# Pendulum_Lamp_PCB.net
KiCad netlist of a schematic drawn in EAGLE
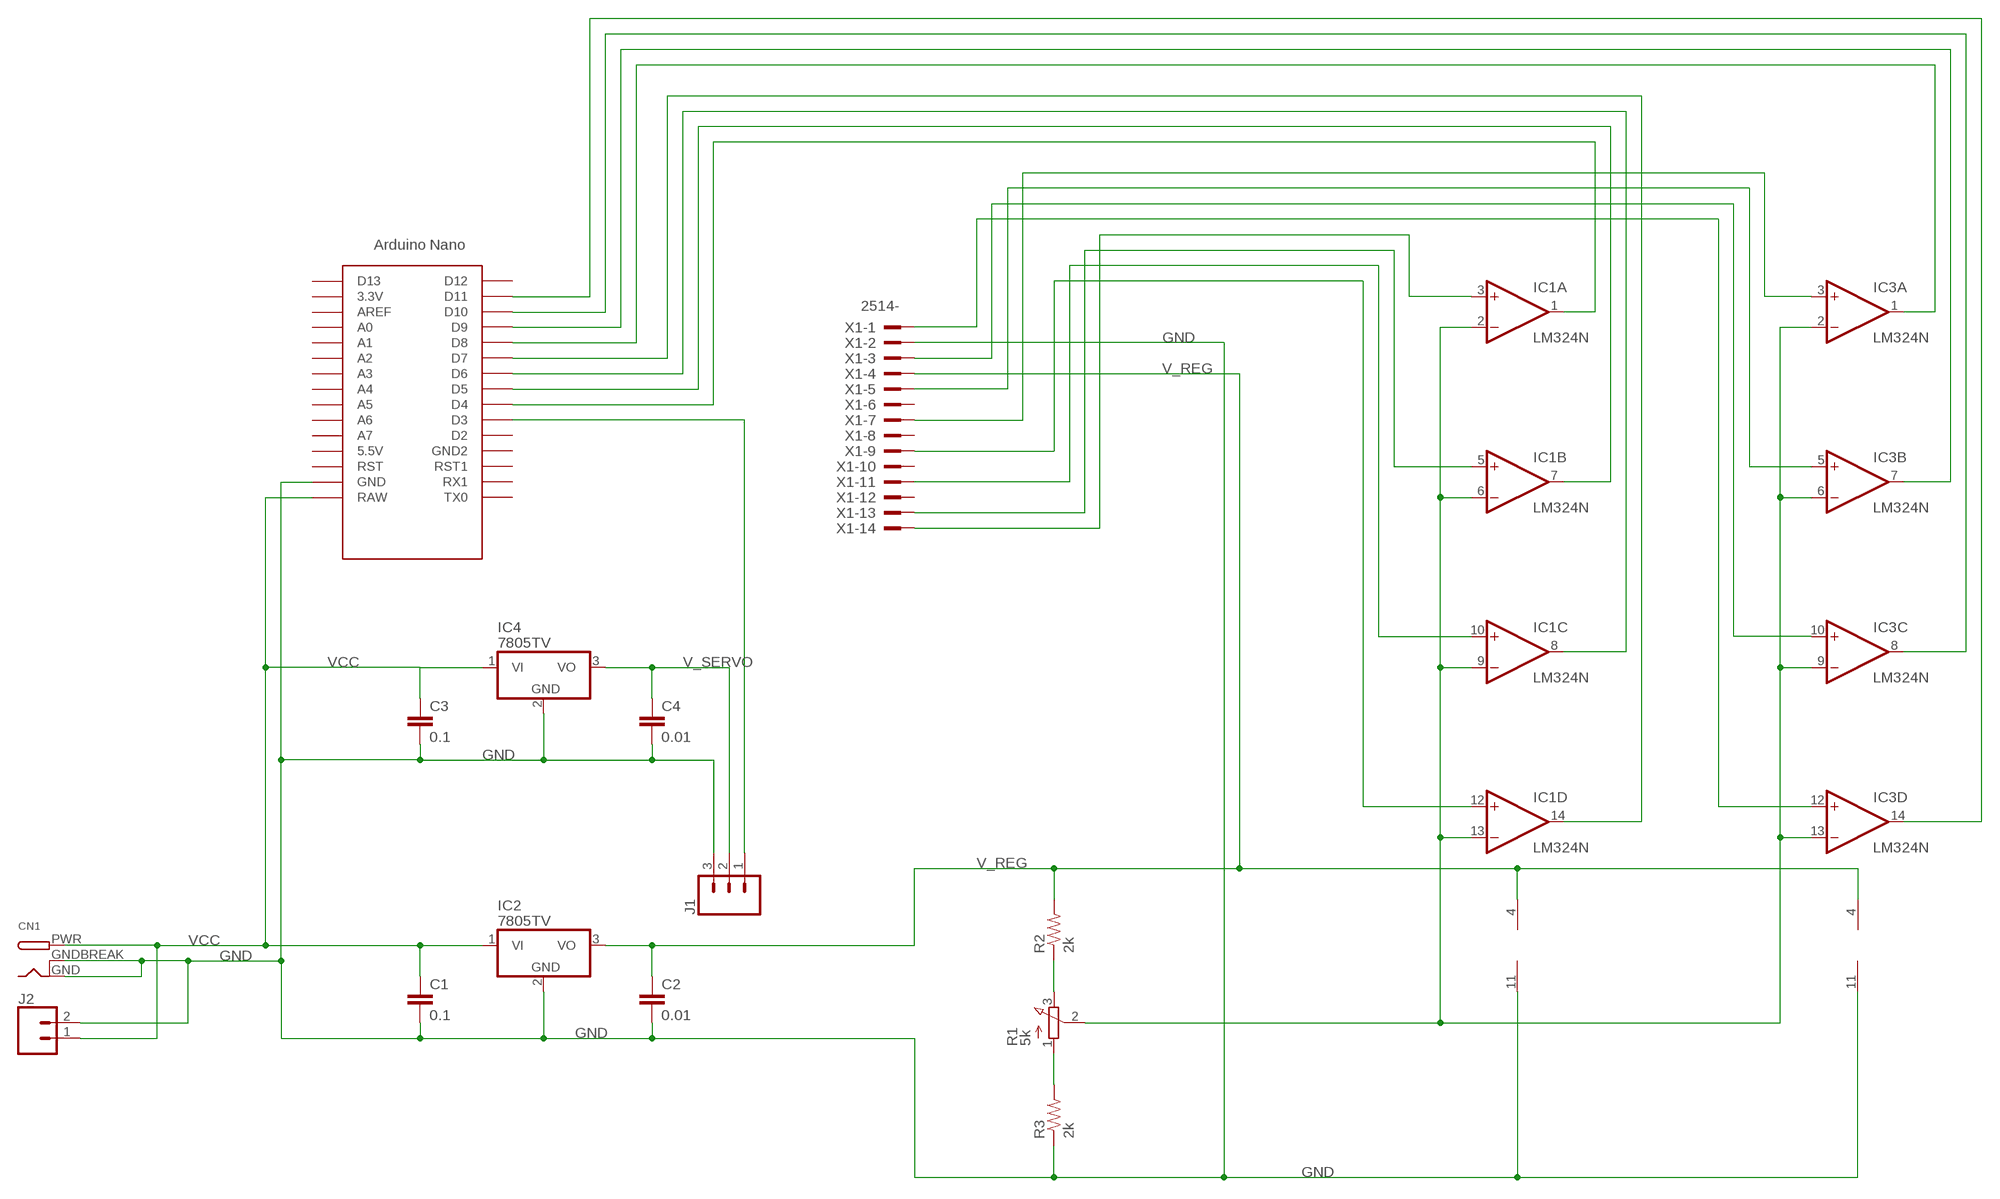
[diagram p0: schematic, sheet 1]
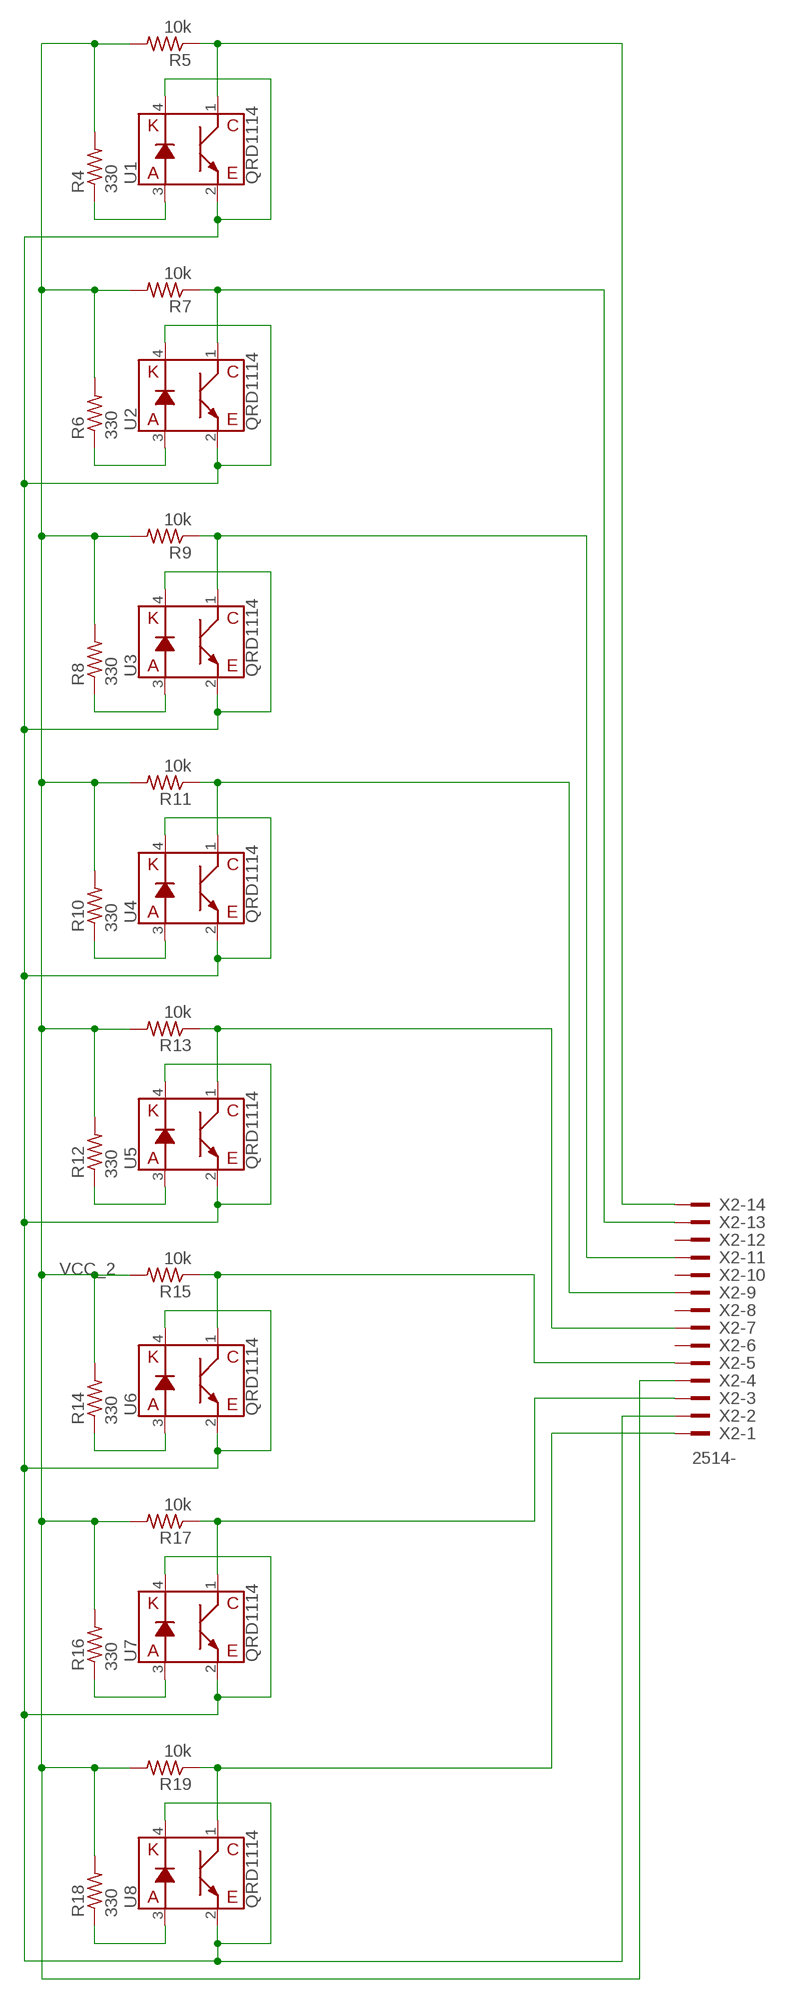
[diagram p1: schematic, sheet 2]

(export (version "E")
  (design (tool "Eeschema 10.0.6"))
  (components
    (comp (ref "R4")
      (value "330")
      (footprint "eagle-import:0204_7")
      (libsource (lib "eagle-import") (part "R-US_0204/7"))
    )
    (comp (ref "R5")
      (value "10k")
      (footprint "eagle-import:0204_7")
      (libsource (lib "eagle-import") (part "R-US_0204/7"))
    )
    (comp (ref "R6")
      (value "330")
      (footprint "eagle-import:0204_7")
      (libsource (lib "eagle-import") (part "R-US_0204/7"))
    )
    (comp (ref "R7")
      (value "10k")
      (footprint "eagle-import:0204_7")
      (libsource (lib "eagle-import") (part "R-US_0204/7"))
    )
    (comp (ref "R8")
      (value "330")
      (footprint "eagle-import:0204_7")
      (libsource (lib "eagle-import") (part "R-US_0204/7"))
    )
    (comp (ref "R9")
      (value "10k")
      (footprint "eagle-import:0204_7")
      (libsource (lib "eagle-import") (part "R-US_0204/7"))
    )
    (comp (ref "R10")
      (value "330")
      (footprint "eagle-import:0204_7")
      (libsource (lib "eagle-import") (part "R-US_0204/7"))
    )
    (comp (ref "R11")
      (value "10k")
      (footprint "eagle-import:0204_7")
      (libsource (lib "eagle-import") (part "R-US_0204/7"))
    )
    (comp (ref "R12")
      (value "330")
      (footprint "eagle-import:0204_7")
      (libsource (lib "eagle-import") (part "R-US_0204/7"))
    )
    (comp (ref "R13")
      (value "10k")
      (footprint "eagle-import:0204_7")
      (libsource (lib "eagle-import") (part "R-US_0204/7"))
    )
    (comp (ref "R14")
      (value "330")
      (footprint "eagle-import:0204_7")
      (libsource (lib "eagle-import") (part "R-US_0204/7"))
    )
    (comp (ref "R15")
      (value "10k")
      (footprint "eagle-import:0204_7")
      (libsource (lib "eagle-import") (part "R-US_0204/7"))
    )
    (comp (ref "R16")
      (value "330")
      (footprint "eagle-import:0204_7")
      (libsource (lib "eagle-import") (part "R-US_0204/7"))
    )
    (comp (ref "R17")
      (value "10k")
      (footprint "eagle-import:0204_7")
      (libsource (lib "eagle-import") (part "R-US_0204/7"))
    )
    (comp (ref "R18")
      (value "330")
      (footprint "eagle-import:0204_7")
      (libsource (lib "eagle-import") (part "R-US_0204/7"))
    )
    (comp (ref "R19")
      (value "10k")
      (footprint "eagle-import:0204_7")
      (libsource (lib "eagle-import") (part "R-US_0204/7"))
    )
    (comp (ref "U1")
      (value "QRD1114")
      (footprint "eagle-import:QRD1114")
      (libsource (lib "eagle-import") (part "QRD1114"))
    )
    (comp (ref "U2")
      (value "QRD1114")
      (footprint "eagle-import:QRD1114")
      (libsource (lib "eagle-import") (part "QRD1114"))
    )
    (comp (ref "U3")
      (value "QRD1114")
      (footprint "eagle-import:QRD1114")
      (libsource (lib "eagle-import") (part "QRD1114"))
    )
    (comp (ref "U4")
      (value "QRD1114")
      (footprint "eagle-import:QRD1114")
      (libsource (lib "eagle-import") (part "QRD1114"))
    )
    (comp (ref "U5")
      (value "QRD1114")
      (footprint "eagle-import:QRD1114")
      (libsource (lib "eagle-import") (part "QRD1114"))
    )
    (comp (ref "U6")
      (value "QRD1114")
      (footprint "eagle-import:QRD1114")
      (libsource (lib "eagle-import") (part "QRD1114"))
    )
    (comp (ref "U7")
      (value "QRD1114")
      (footprint "eagle-import:QRD1114")
      (libsource (lib "eagle-import") (part "QRD1114"))
    )
    (comp (ref "U8")
      (value "QRD1114")
      (footprint "eagle-import:QRD1114")
      (libsource (lib "eagle-import") (part "QRD1114"))
    )
    (comp (ref "X2")
      (value "2514-")
      (footprint "eagle-import:PAK100_2500-14")
      (libsource (lib "eagle-import") (part "2514-"))
    )
    (comp (ref "C1")
      (value "0.1")
      (footprint "eagle-import:C025-030X050")
      (libsource (lib "eagle-import") (part "C-EU025-030X050"))
    )
    (comp (ref "C2")
      (value "0.01")
      (footprint "eagle-import:C025-030X050")
      (libsource (lib "eagle-import") (part "C-EU025-030X050"))
    )
    (comp (ref "C3")
      (value "0.1")
      (footprint "eagle-import:C025-030X050")
      (libsource (lib "eagle-import") (part "C-EU025-030X050"))
    )
    (comp (ref "C4")
      (value "0.01")
      (footprint "eagle-import:C025-030X050")
      (libsource (lib "eagle-import") (part "C-EU025-030X050"))
    )
    (comp (ref "CN1")
      (value "DCBARRELPTH")
      (footprint "eagle-import:DCJACK_2MM_PTH")
      (libsource (lib "eagle-import") (part "DCBARRELPTH"))
    )
    (comp (ref "IC1")
      (value "LM324N")
      (footprint "eagle-import:DIL14")
      (libsource (lib "eagle-import") (part "LM324N"))
    )
    (comp (ref "IC2")
      (value "7805TV")
      (footprint "eagle-import:TO220V")
      (libsource (lib "eagle-import") (part "78TV05"))
    )
    (comp (ref "IC3")
      (value "LM324N")
      (footprint "eagle-import:DIL14")
      (libsource (lib "eagle-import") (part "LM324N"))
    )
    (comp (ref "IC4")
      (value "7805TV")
      (footprint "eagle-import:TO220V")
      (libsource (lib "eagle-import") (part "78TV05"))
    )
    (comp (ref "J1")
      (value "CONN_03LONGPADS")
      (footprint "eagle-import:1X03_LONGPADS")
      (libsource (lib "eagle-import") (part "CONN_03LONGPADS"))
    )
    (comp (ref "J2")
      (value "CONN_023.5MM_LOCK")
      (footprint "eagle-import:SCREWTERMINAL-3.5MM-2_LOCK")
      (libsource (lib "eagle-import") (part "CONN_023.5MM_LOCK"))
    )
    (comp (ref "R1")
      (value "5k")
      (footprint "eagle-import:3RP_1610N")
      (libsource (lib "eagle-import") (part "3RP/1610N"))
    )
    (comp (ref "R2")
      (value "2k")
      (footprint "eagle-import:0204_7")
      (libsource (lib "eagle-import") (part "R-US_0204/7"))
    )
    (comp (ref "R3")
      (value "2k")
      (footprint "eagle-import:0204_7")
      (libsource (lib "eagle-import") (part "R-US_0204/7"))
    )
    (comp (ref "U$1")
      (value "NANO")
      (footprint "eagle-import:NANO")
      (libsource (lib "eagle-import") (part "NANO"))
    )
    (comp (ref "X1")
      (value "2514-")
      (footprint "eagle-import:PAK100_2500-14")
      (libsource (lib "eagle-import") (part "2514-"))
    )
  )
  (nets
    (net (code "1") (name "GND") (class "Default")
      (node (ref "C1") (pin "2") (pinfunction "2_2") (pintype "passive"))
      (node (ref "C2") (pin "2") (pinfunction "2_2") (pintype "passive"))
      (node (ref "C3") (pin "2") (pinfunction "2_2") (pintype "passive"))
      (node (ref "C4") (pin "2") (pinfunction "2_2") (pintype "passive"))
      (node (ref "CN1") (pin "GND") (pinfunction "GND_GND") (pintype "power_in"))
      (node (ref "CN1") (pin "GNDBREAK") (pinfunction "GNDBREAK_GNDBREAK") (pintype "power_in"))
      (node (ref "IC1") (pin "11") (pinfunction "V-_11") (pintype "power_in"))
      (node (ref "IC2") (pin "2") (pinfunction "GND_2") (pintype "passive"))
      (node (ref "IC3") (pin "11") (pinfunction "V-_11") (pintype "power_in"))
      (node (ref "IC4") (pin "2") (pinfunction "GND_2") (pintype "passive"))
      (node (ref "J1") (pin "3") (pinfunction "3_3") (pintype "passive"))
      (node (ref "J2") (pin "2") (pinfunction "2_2") (pintype "passive"))
      (node (ref "R3") (pin "1") (pinfunction "1_1") (pintype "passive"))
      (node (ref "U$1") (pin "GND") (pinfunction "GND_GND") (pintype "bidirectional"))
      (node (ref "X1") (pin "2") (pinfunction "KL_2") (pintype "passive"))
    )
    (net (code "2") (name "Net-(IC1A-+IN)") (class "Default")
      (node (ref "IC1") (pin "3") (pinfunction "+IN_3") (pintype "input"))
      (node (ref "X1") (pin "14") (pinfunction "KL_14") (pintype "passive"))
    )
    (net (code "3") (name "Net-(IC1A--IN)") (class "Default")
      (node (ref "IC1") (pin "13") (pinfunction "-IN_13") (pintype "input"))
      (node (ref "IC1") (pin "2") (pinfunction "-IN_2") (pintype "input"))
      (node (ref "IC1") (pin "6") (pinfunction "-IN_6") (pintype "input"))
      (node (ref "IC1") (pin "9") (pinfunction "-IN_9") (pintype "input"))
      (node (ref "IC3") (pin "13") (pinfunction "-IN_13") (pintype "input"))
      (node (ref "IC3") (pin "2") (pinfunction "-IN_2") (pintype "input"))
      (node (ref "IC3") (pin "6") (pinfunction "-IN_6") (pintype "input"))
      (node (ref "IC3") (pin "9") (pinfunction "-IN_9") (pintype "input"))
      (node (ref "R1") (pin "2") (pinfunction "S_2") (pintype "passive"))
    )
    (net (code "4") (name "Net-(IC1A-OUT)") (class "Default")
      (node (ref "IC1") (pin "1") (pinfunction "OUT_1") (pintype "output"))
      (node (ref "U$1") (pin "D4") (pinfunction "D4_D4") (pintype "bidirectional"))
    )
    (net (code "5") (name "Net-(IC1B-+IN)") (class "Default")
      (node (ref "IC1") (pin "5") (pinfunction "+IN_5") (pintype "input"))
      (node (ref "X1") (pin "13") (pinfunction "KL_13") (pintype "passive"))
    )
    (net (code "6") (name "Net-(IC1B-OUT)") (class "Default")
      (node (ref "IC1") (pin "7") (pinfunction "OUT_7") (pintype "output"))
      (node (ref "U$1") (pin "D5") (pinfunction "D5_D5") (pintype "bidirectional"))
    )
    (net (code "7") (name "Net-(IC1C-+IN)") (class "Default")
      (node (ref "IC1") (pin "10") (pinfunction "+IN_10") (pintype "input"))
      (node (ref "X1") (pin "11") (pinfunction "KL_11") (pintype "passive"))
    )
    (net (code "8") (name "Net-(IC1C-OUT)") (class "Default")
      (node (ref "IC1") (pin "8") (pinfunction "OUT_8") (pintype "output"))
      (node (ref "U$1") (pin "D6") (pinfunction "D6_D6") (pintype "bidirectional"))
    )
    (net (code "9") (name "Net-(IC1D-+IN)") (class "Default")
      (node (ref "IC1") (pin "12") (pinfunction "+IN_12") (pintype "input"))
      (node (ref "X1") (pin "9") (pinfunction "KL_9") (pintype "passive"))
    )
    (net (code "10") (name "Net-(IC1D-OUT)") (class "Default")
      (node (ref "IC1") (pin "14") (pinfunction "OUT_14") (pintype "output"))
      (node (ref "U$1") (pin "D7") (pinfunction "D7_D7") (pintype "bidirectional"))
    )
    (net (code "11") (name "Net-(IC3A-+IN)") (class "Default")
      (node (ref "IC3") (pin "3") (pinfunction "+IN_3") (pintype "input"))
      (node (ref "X1") (pin "7") (pinfunction "KL_7") (pintype "passive"))
    )
    (net (code "12") (name "Net-(IC3A-OUT)") (class "Default")
      (node (ref "IC3") (pin "1") (pinfunction "OUT_1") (pintype "output"))
      (node (ref "U$1") (pin "D8") (pinfunction "D8_D8") (pintype "bidirectional"))
    )
    (net (code "13") (name "Net-(IC3B-+IN)") (class "Default")
      (node (ref "IC3") (pin "5") (pinfunction "+IN_5") (pintype "input"))
      (node (ref "X1") (pin "5") (pinfunction "KL_5") (pintype "passive"))
    )
    (net (code "14") (name "Net-(IC3B-OUT)") (class "Default")
      (node (ref "IC3") (pin "7") (pinfunction "OUT_7") (pintype "output"))
      (node (ref "U$1") (pin "D9") (pinfunction "D9_D9") (pintype "bidirectional"))
    )
    (net (code "15") (name "Net-(IC3C-+IN)") (class "Default")
      (node (ref "IC3") (pin "10") (pinfunction "+IN_10") (pintype "input"))
      (node (ref "X1") (pin "3") (pinfunction "KL_3") (pintype "passive"))
    )
    (net (code "16") (name "Net-(IC3C-OUT)") (class "Default")
      (node (ref "IC3") (pin "8") (pinfunction "OUT_8") (pintype "output"))
      (node (ref "U$1") (pin "D10") (pinfunction "D10_D10") (pintype "bidirectional"))
    )
    (net (code "17") (name "Net-(IC3D-+IN)") (class "Default")
      (node (ref "IC3") (pin "12") (pinfunction "+IN_12") (pintype "input"))
      (node (ref "X1") (pin "1") (pinfunction "KL_1") (pintype "passive"))
    )
    (net (code "18") (name "Net-(IC3D-OUT)") (class "Default")
      (node (ref "IC3") (pin "14") (pinfunction "OUT_14") (pintype "output"))
      (node (ref "U$1") (pin "D11") (pinfunction "D11_D11") (pintype "bidirectional"))
    )
    (net (code "19") (name "Net-(J1-Pad1)") (class "Default")
      (node (ref "J1") (pin "1") (pinfunction "1_1") (pintype "passive"))
      (node (ref "U$1") (pin "D3") (pinfunction "D3_D3") (pintype "bidirectional"))
    )
    (net (code "20") (name "Net-(R1-A)") (class "Default")
      (node (ref "R1") (pin "1") (pinfunction "A_1") (pintype "passive"))
      (node (ref "R3") (pin "2") (pinfunction "2_2") (pintype "passive"))
    )
    (net (code "21") (name "Net-(R1-E)") (class "Default")
      (node (ref "R1") (pin "3") (pinfunction "E_3") (pintype "passive"))
      (node (ref "R2") (pin "1") (pinfunction "1_1") (pintype "passive"))
    )
    (net (code "22") (name "Net-(U1-A)") (class "Default")
      (node (ref "R4") (pin "1") (pinfunction "1_1") (pintype "passive"))
      (node (ref "U1") (pin "3") (pinfunction "A_3") (pintype "bidirectional"))
    )
    (net (code "23") (name "Net-(U1-C)") (class "Default")
      (node (ref "R5") (pin "1") (pinfunction "1_1") (pintype "passive"))
      (node (ref "U1") (pin "1") (pinfunction "C_1") (pintype "bidirectional"))
      (node (ref "X2") (pin "14") (pinfunction "KL_14") (pintype "passive"))
    )
    (net (code "24") (name "Net-(U1-E)") (class "Default")
      (node (ref "U1") (pin "2") (pinfunction "E_2") (pintype "bidirectional"))
      (node (ref "U1") (pin "4") (pinfunction "K_4") (pintype "bidirectional"))
      (node (ref "U2") (pin "2") (pinfunction "E_2") (pintype "bidirectional"))
      (node (ref "U2") (pin "4") (pinfunction "K_4") (pintype "bidirectional"))
      (node (ref "U3") (pin "2") (pinfunction "E_2") (pintype "bidirectional"))
      (node (ref "U3") (pin "4") (pinfunction "K_4") (pintype "bidirectional"))
      (node (ref "U4") (pin "2") (pinfunction "E_2") (pintype "bidirectional"))
      (node (ref "U4") (pin "4") (pinfunction "K_4") (pintype "bidirectional"))
      (node (ref "U5") (pin "2") (pinfunction "E_2") (pintype "bidirectional"))
      (node (ref "U5") (pin "4") (pinfunction "K_4") (pintype "bidirectional"))
      (node (ref "U6") (pin "2") (pinfunction "E_2") (pintype "bidirectional"))
      (node (ref "U6") (pin "4") (pinfunction "K_4") (pintype "bidirectional"))
      (node (ref "U7") (pin "2") (pinfunction "E_2") (pintype "bidirectional"))
      (node (ref "U7") (pin "4") (pinfunction "K_4") (pintype "bidirectional"))
      (node (ref "U8") (pin "2") (pinfunction "E_2") (pintype "bidirectional"))
      (node (ref "U8") (pin "4") (pinfunction "K_4") (pintype "bidirectional"))
      (node (ref "X2") (pin "2") (pinfunction "KL_2") (pintype "passive"))
    )
    (net (code "25") (name "Net-(U2-A)") (class "Default")
      (node (ref "R6") (pin "1") (pinfunction "1_1") (pintype "passive"))
      (node (ref "U2") (pin "3") (pinfunction "A_3") (pintype "bidirectional"))
    )
    (net (code "26") (name "Net-(U2-C)") (class "Default")
      (node (ref "R7") (pin "1") (pinfunction "1_1") (pintype "passive"))
      (node (ref "U2") (pin "1") (pinfunction "C_1") (pintype "bidirectional"))
      (node (ref "X2") (pin "13") (pinfunction "KL_13") (pintype "passive"))
    )
    (net (code "27") (name "Net-(U3-A)") (class "Default")
      (node (ref "R8") (pin "1") (pinfunction "1_1") (pintype "passive"))
      (node (ref "U3") (pin "3") (pinfunction "A_3") (pintype "bidirectional"))
    )
    (net (code "28") (name "Net-(U3-C)") (class "Default")
      (node (ref "R9") (pin "1") (pinfunction "1_1") (pintype "passive"))
      (node (ref "U3") (pin "1") (pinfunction "C_1") (pintype "bidirectional"))
      (node (ref "X2") (pin "11") (pinfunction "KL_11") (pintype "passive"))
    )
    (net (code "29") (name "Net-(U4-A)") (class "Default")
      (node (ref "R10") (pin "1") (pinfunction "1_1") (pintype "passive"))
      (node (ref "U4") (pin "3") (pinfunction "A_3") (pintype "bidirectional"))
    )
    (net (code "30") (name "Net-(U4-C)") (class "Default")
      (node (ref "R11") (pin "1") (pinfunction "1_1") (pintype "passive"))
      (node (ref "U4") (pin "1") (pinfunction "C_1") (pintype "bidirectional"))
      (node (ref "X2") (pin "9") (pinfunction "KL_9") (pintype "passive"))
    )
    (net (code "31") (name "Net-(U5-A)") (class "Default")
      (node (ref "R12") (pin "1") (pinfunction "1_1") (pintype "passive"))
      (node (ref "U5") (pin "3") (pinfunction "A_3") (pintype "bidirectional"))
    )
    (net (code "32") (name "Net-(U5-C)") (class "Default")
      (node (ref "R13") (pin "1") (pinfunction "1_1") (pintype "passive"))
      (node (ref "U5") (pin "1") (pinfunction "C_1") (pintype "bidirectional"))
      (node (ref "X2") (pin "7") (pinfunction "KL_7") (pintype "passive"))
    )
    (net (code "33") (name "Net-(U6-A)") (class "Default")
      (node (ref "R14") (pin "1") (pinfunction "1_1") (pintype "passive"))
      (node (ref "U6") (pin "3") (pinfunction "A_3") (pintype "bidirectional"))
    )
    (net (code "34") (name "Net-(U6-C)") (class "Default")
      (node (ref "R15") (pin "1") (pinfunction "1_1") (pintype "passive"))
      (node (ref "U6") (pin "1") (pinfunction "C_1") (pintype "bidirectional"))
      (node (ref "X2") (pin "5") (pinfunction "KL_5") (pintype "passive"))
    )
    (net (code "35") (name "Net-(U7-A)") (class "Default")
      (node (ref "R16") (pin "1") (pinfunction "1_1") (pintype "passive"))
      (node (ref "U7") (pin "3") (pinfunction "A_3") (pintype "bidirectional"))
    )
    (net (code "36") (name "Net-(U7-C)") (class "Default")
      (node (ref "R17") (pin "1") (pinfunction "1_1") (pintype "passive"))
      (node (ref "U7") (pin "1") (pinfunction "C_1") (pintype "bidirectional"))
      (node (ref "X2") (pin "3") (pinfunction "KL_3") (pintype "passive"))
    )
    (net (code "37") (name "Net-(U8-A)") (class "Default")
      (node (ref "R18") (pin "1") (pinfunction "1_1") (pintype "passive"))
      (node (ref "U8") (pin "3") (pinfunction "A_3") (pintype "bidirectional"))
    )
    (net (code "38") (name "Net-(U8-C)") (class "Default")
      (node (ref "R19") (pin "1") (pinfunction "1_1") (pintype "passive"))
      (node (ref "U8") (pin "1") (pinfunction "C_1") (pintype "bidirectional"))
      (node (ref "X2") (pin "1") (pinfunction "KL_1") (pintype "passive"))
    )
    (net (code "39") (name "VCC") (class "Default")
      (node (ref "C1") (pin "1") (pinfunction "1_1") (pintype "passive"))
      (node (ref "C3") (pin "1") (pinfunction "1_1") (pintype "passive"))
      (node (ref "CN1") (pin "PWR") (pinfunction "PWR_PWR") (pintype "power_in"))
      (node (ref "IC2") (pin "1") (pinfunction "VI_1") (pintype "input"))
      (node (ref "IC4") (pin "1") (pinfunction "VI_1") (pintype "input"))
      (node (ref "J2") (pin "1") (pinfunction "1_1") (pintype "passive"))
      (node (ref "U$1") (pin "RAW") (pinfunction "RAW_RAW") (pintype "bidirectional"))
    )
    (net (code "40") (name "VCC_2") (class "Default")
      (node (ref "R10") (pin "2") (pinfunction "2_2") (pintype "passive"))
      (node (ref "R11") (pin "2") (pinfunction "2_2") (pintype "passive"))
      (node (ref "R12") (pin "2") (pinfunction "2_2") (pintype "passive"))
      (node (ref "R13") (pin "2") (pinfunction "2_2") (pintype "passive"))
      (node (ref "R14") (pin "2") (pinfunction "2_2") (pintype "passive"))
      (node (ref "R15") (pin "2") (pinfunction "2_2") (pintype "passive"))
      (node (ref "R16") (pin "2") (pinfunction "2_2") (pintype "passive"))
      (node (ref "R17") (pin "2") (pinfunction "2_2") (pintype "passive"))
      (node (ref "R18") (pin "2") (pinfunction "2_2") (pintype "passive"))
      (node (ref "R19") (pin "2") (pinfunction "2_2") (pintype "passive"))
      (node (ref "R4") (pin "2") (pinfunction "2_2") (pintype "passive"))
      (node (ref "R5") (pin "2") (pinfunction "2_2") (pintype "passive"))
      (node (ref "R6") (pin "2") (pinfunction "2_2") (pintype "passive"))
      (node (ref "R7") (pin "2") (pinfunction "2_2") (pintype "passive"))
      (node (ref "R8") (pin "2") (pinfunction "2_2") (pintype "passive"))
      (node (ref "R9") (pin "2") (pinfunction "2_2") (pintype "passive"))
      (node (ref "X2") (pin "4") (pinfunction "KL_4") (pintype "passive"))
    )
    (net (code "41") (name "V_REG") (class "Default")
      (node (ref "C2") (pin "1") (pinfunction "1_1") (pintype "passive"))
      (node (ref "IC1") (pin "4") (pinfunction "V+_4") (pintype "power_in"))
      (node (ref "IC2") (pin "3") (pinfunction "VO_3") (pintype "passive"))
      (node (ref "IC3") (pin "4") (pinfunction "V+_4") (pintype "power_in"))
      (node (ref "R2") (pin "2") (pinfunction "2_2") (pintype "passive"))
      (node (ref "X1") (pin "4") (pinfunction "KL_4") (pintype "passive"))
    )
    (net (code "42") (name "V_SERVO") (class "Default")
      (node (ref "C4") (pin "1") (pinfunction "1_1") (pintype "passive"))
      (node (ref "IC4") (pin "3") (pinfunction "VO_3") (pintype "passive"))
      (node (ref "J1") (pin "2") (pinfunction "2_2") (pintype "passive"))
    )
    (net (code "43") (name "unconnected-(U$1-5.5V-Pad5V)") (class "Default")
      (node (ref "U$1") (pin "5V") (pinfunction "5.5V_5V") (pintype "bidirectional"))
    )
    (net (code "44") (name "unconnected-(U$1-GND2-PadGND1)") (class "Default")
      (node (ref "U$1") (pin "GND1") (pinfunction "GND2_GND1") (pintype "bidirectional"))
    )
    (net (code "45") (name "unconnected-(U$1-Pad3.3V)") (class "Default")
      (node (ref "U$1") (pin "3.3V") (pinfunction "3.3V_3.3V") (pintype "bidirectional"))
    )
    (net (code "46") (name "unconnected-(U$1-PadA0)") (class "Default")
      (node (ref "U$1") (pin "A0") (pinfunction "A0_A0") (pintype "bidirectional"))
    )
    (net (code "47") (name "unconnected-(U$1-PadA1)") (class "Default")
      (node (ref "U$1") (pin "A1") (pinfunction "A1_A1") (pintype "bidirectional"))
    )
    (net (code "48") (name "unconnected-(U$1-PadA2)") (class "Default")
      (node (ref "U$1") (pin "A2") (pinfunction "A2_A2") (pintype "bidirectional"))
    )
    (net (code "49") (name "unconnected-(U$1-PadA3)") (class "Default")
      (node (ref "U$1") (pin "A3") (pinfunction "A3_A3") (pintype "bidirectional"))
    )
    (net (code "50") (name "unconnected-(U$1-PadA4)") (class "Default")
      (node (ref "U$1") (pin "A4") (pinfunction "A4_A4") (pintype "bidirectional"))
    )
    (net (code "51") (name "unconnected-(U$1-PadA5)") (class "Default")
      (node (ref "U$1") (pin "A5") (pinfunction "A5_A5") (pintype "bidirectional"))
    )
    (net (code "52") (name "unconnected-(U$1-PadA6)") (class "Default")
      (node (ref "U$1") (pin "A6") (pinfunction "A6_A6") (pintype "bidirectional"))
    )
    (net (code "53") (name "unconnected-(U$1-PadA7)") (class "Default")
      (node (ref "U$1") (pin "A7") (pinfunction "A7_A7") (pintype "bidirectional"))
    )
    (net (code "54") (name "unconnected-(U$1-PadAREF)") (class "Default")
      (node (ref "U$1") (pin "AREF") (pinfunction "AREF_AREF") (pintype "bidirectional"))
    )
    (net (code "55") (name "unconnected-(U$1-PadD2)") (class "Default")
      (node (ref "U$1") (pin "D2") (pinfunction "D2_D2") (pintype "bidirectional"))
    )
    (net (code "56") (name "unconnected-(U$1-PadD12)") (class "Default")
      (node (ref "U$1") (pin "D12") (pinfunction "D12_D12") (pintype "bidirectional"))
    )
    (net (code "57") (name "unconnected-(U$1-PadD13)") (class "Default")
      (node (ref "U$1") (pin "D13") (pinfunction "D13_D13") (pintype "bidirectional"))
    )
    (net (code "58") (name "unconnected-(U$1-PadICSP1)") (class "Default")
      (node (ref "U$1") (pin "ICSP1") (pinfunction "ICSP1_ICSP1") (pintype "bidirectional"))
    )
    (net (code "59") (name "unconnected-(U$1-PadICSP2)") (class "Default")
      (node (ref "U$1") (pin "ICSP2") (pinfunction "ICSP2_ICSP2") (pintype "bidirectional"))
    )
    (net (code "60") (name "unconnected-(U$1-PadICSP3)") (class "Default")
      (node (ref "U$1") (pin "ICSP3") (pinfunction "ICSP3_ICSP3") (pintype "bidirectional"))
    )
    (net (code "61") (name "unconnected-(U$1-PadICSP4)") (class "Default")
      (node (ref "U$1") (pin "ICSP4") (pinfunction "ICSP4_ICSP4") (pintype "bidirectional"))
    )
    (net (code "62") (name "unconnected-(U$1-PadICSP5)") (class "Default")
      (node (ref "U$1") (pin "ICSP5") (pinfunction "ICSP5_ICSP5") (pintype "bidirectional"))
    )
    (net (code "63") (name "unconnected-(U$1-PadICSP6)") (class "Default")
      (node (ref "U$1") (pin "ICSP6") (pinfunction "ICSP6_ICSP6") (pintype "bidirectional"))
    )
    (net (code "64") (name "unconnected-(U$1-PadRST)") (class "Default")
      (node (ref "U$1") (pin "RST") (pinfunction "RST_RST") (pintype "bidirectional"))
    )
    (net (code "65") (name "unconnected-(U$1-PadRST1)") (class "Default")
      (node (ref "U$1") (pin "RST1") (pinfunction "RST1_RST1") (pintype "bidirectional"))
    )
    (net (code "66") (name "unconnected-(U$1-PadRX1)") (class "Default")
      (node (ref "U$1") (pin "RX1") (pinfunction "RX1_RX1") (pintype "bidirectional"))
    )
    (net (code "67") (name "unconnected-(U$1-PadTX0)") (class "Default")
      (node (ref "U$1") (pin "TX0") (pinfunction "TX0_TX0") (pintype "bidirectional"))
    )
    (net (code "68") (name "unconnected-(X1B-KL-Pad10)") (class "Default")
      (node (ref "X1") (pin "10") (pinfunction "KL_10") (pintype "passive"))
    )
    (net (code "69") (name "unconnected-(X1D-KL-Pad12)") (class "Default")
      (node (ref "X1") (pin "12") (pinfunction "KL_12") (pintype "passive"))
    )
    (net (code "70") (name "unconnected-(X1K-KL-Pad6)") (class "Default")
      (node (ref "X1") (pin "6") (pinfunction "KL_6") (pintype "passive"))
    )
    (net (code "71") (name "unconnected-(X1M-KL-Pad8)") (class "Default")
      (node (ref "X1") (pin "8") (pinfunction "KL_8") (pintype "passive"))
    )
    (net (code "72") (name "unconnected-(X2B-KL-Pad10)") (class "Default")
      (node (ref "X2") (pin "10") (pinfunction "KL_10") (pintype "passive"))
    )
    (net (code "73") (name "unconnected-(X2D-KL-Pad12)") (class "Default")
      (node (ref "X2") (pin "12") (pinfunction "KL_12") (pintype "passive"))
    )
    (net (code "74") (name "unconnected-(X2K-KL-Pad6)") (class "Default")
      (node (ref "X2") (pin "6") (pinfunction "KL_6") (pintype "passive"))
    )
    (net (code "75") (name "unconnected-(X2M-KL-Pad8)") (class "Default")
      (node (ref "X2") (pin "8") (pinfunction "KL_8") (pintype "passive"))
    )
  )
)
